# Bullseye_Volume_Board_Rev_0_0_3.net
KiCad netlist of a schematic drawn in Altium Designer
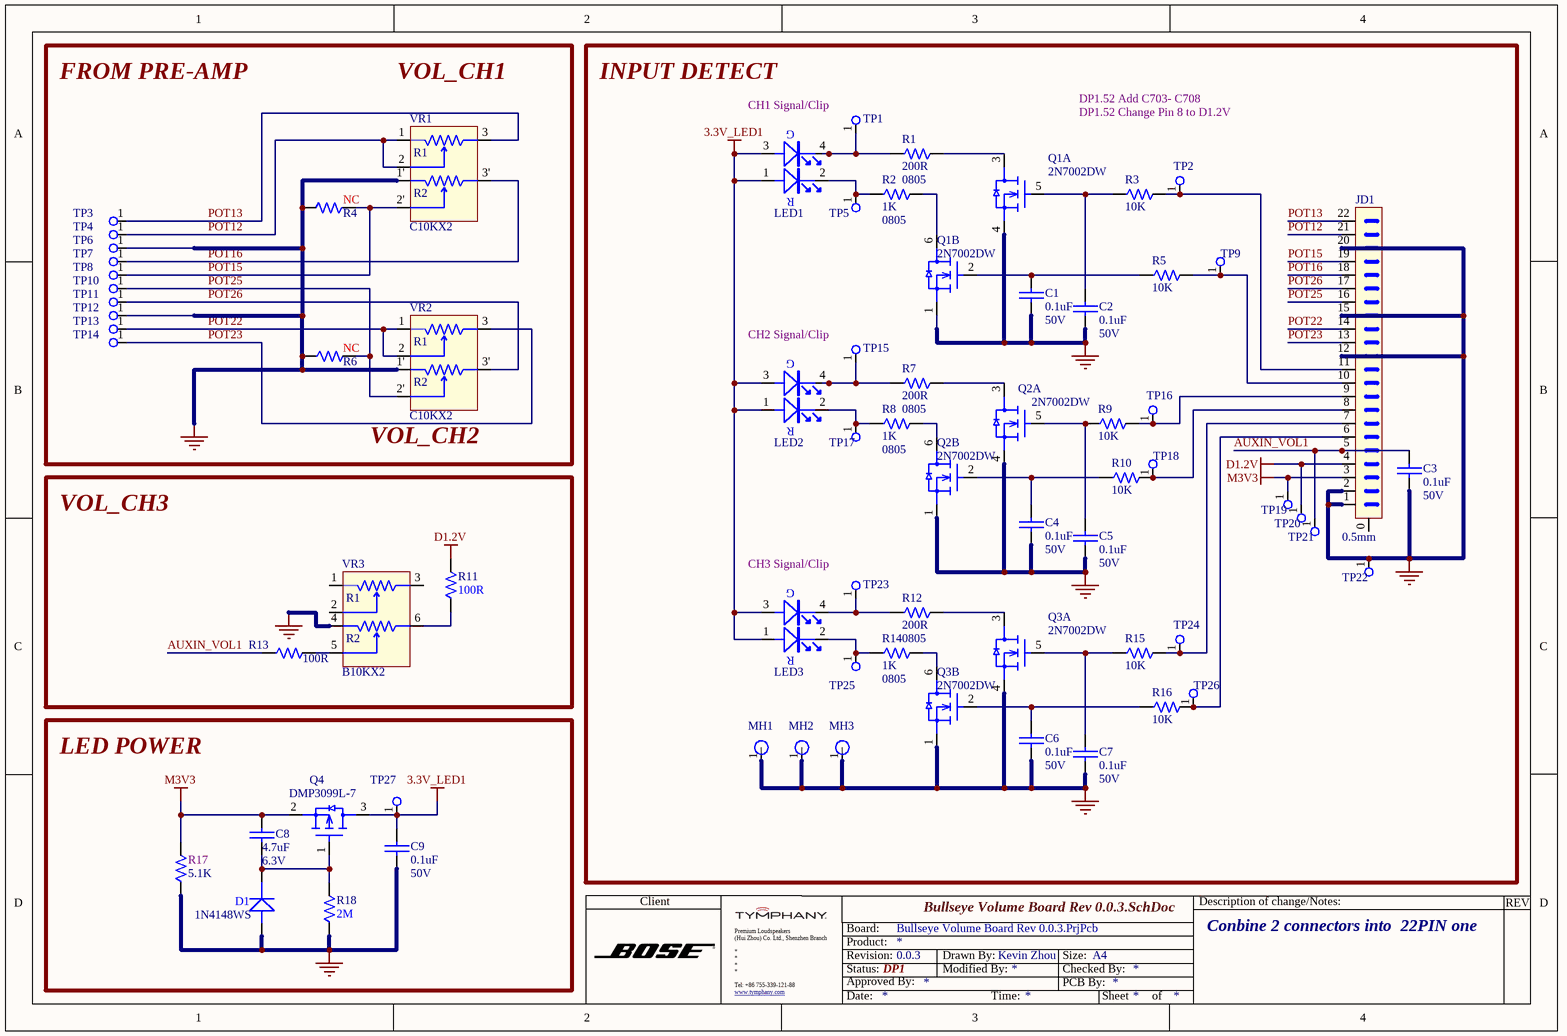
[diagram p0: Bullseye Volume Board Rev 0.0.3.SchDoc]

(export (version "E")
  (design (tool "Eeschema 10.0.6"))
  (components
    (comp (ref "C1")
      (value "0.1uF")
      (footprint "CAPC0402-RW")
      (description "CAP, CER, 0.1uF, 10%, 50V, X7R, 0402, RoHS")
      (fields
        (field (name "TOLERANCE") "10%")
        (field (name "VOLTAGE") "50V")
        (field (name "Comment") "PWL456470-1040")
        (field (name "CREATE_NAME") "TOM@Deftronics")
      )
      (libsource (lib "P-Capacitors") (part "CAP0402 0.1uF 50V 10%"))
    )
    (comp (ref "C2")
      (value "0.1uF")
      (footprint "CAPC0402-RW")
      (description "CAP, CER, 0.1uF, 10%, 50V, X7R, 0402, RoHS")
      (fields
        (field (name "TOLERANCE") "10%")
        (field (name "VOLTAGE") "50V")
        (field (name "Comment") "PWL456470-1040")
        (field (name "CREATE_NAME") "TOM@Deftronics")
      )
      (libsource (lib "P-Capacitors") (part "CAP0402 0.1uF 50V 10%"))
    )
    (comp (ref "C3")
      (value "0.1uF")
      (footprint "CAPC0402-RW")
      (description "CAP, CER, 0.1uF, 10%, 50V, X7R, 0402, RoHS")
      (fields
        (field (name "TOLERANCE") "10%")
        (field (name "VOLTAGE") "50V")
        (field (name "Comment") "PWL456470-1040")
        (field (name "CREATE_NAME") "TOM@Deftronics")
      )
      (libsource (lib "P-Capacitors") (part "CAP0402 0.1uF 50V 10%"))
    )
    (comp (ref "C4")
      (value "0.1uF")
      (footprint "CAPC0402-RW")
      (description "CAP, CER, 0.1uF, 10%, 50V, X7R, 0402, RoHS")
      (fields
        (field (name "TOLERANCE") "10%")
        (field (name "VOLTAGE") "50V")
        (field (name "Comment") "PWL456470-1040")
        (field (name "CREATE_NAME") "TOM@Deftronics")
      )
      (libsource (lib "P-Capacitors") (part "CAP0402 0.1uF 50V 10%"))
    )
    (comp (ref "C5")
      (value "0.1uF")
      (footprint "CAPC0402-RW")
      (description "CAP, CER, 0.1uF, 10%, 50V, X7R, 0402, RoHS")
      (fields
        (field (name "TOLERANCE") "10%")
        (field (name "VOLTAGE") "50V")
        (field (name "Comment") "PWL456470-1040")
        (field (name "CREATE_NAME") "TOM@Deftronics")
      )
      (libsource (lib "P-Capacitors") (part "CAP0402 0.1uF 50V 10%"))
    )
    (comp (ref "C6")
      (value "0.1uF")
      (footprint "CAPC0402-RW")
      (description "CAP, CER, 0.1uF, 10%, 50V, X7R, 0402, RoHS")
      (fields
        (field (name "TOLERANCE") "10%")
        (field (name "VOLTAGE") "50V")
        (field (name "Comment") "PWL456470-1040")
        (field (name "CREATE_NAME") "TOM@Deftronics")
      )
      (libsource (lib "P-Capacitors") (part "CAP0402 0.1uF 50V 10%"))
    )
    (comp (ref "C7")
      (value "0.1uF")
      (footprint "CAPC0402-RW")
      (description "CAP, CER, 0.1uF, 10%, 50V, X7R, 0402, RoHS")
      (fields
        (field (name "TOLERANCE") "10%")
        (field (name "VOLTAGE") "50V")
        (field (name "Comment") "PWL456470-1040")
        (field (name "CREATE_NAME") "TOM@Deftronics")
      )
      (libsource (lib "P-Capacitors") (part "CAP0402 0.1uF 50V 10%"))
    )
    (comp (ref "C8")
      (value "4.7uF")
      (footprint "CAPC0603-RW")
      (description "CHIP CAP 4.7uF 6.3V 10% 0603 TYPE X7R")
      (fields (field (name "MFG") "Walsin") (field (name "TOLERANCE") "10%") (field (name "VOLTAGE") "6.3V"))
      (libsource (lib "P-Capacitors") (part "CAP0603 4.7uF 6.3V 10% - Walsin"))
    )
    (comp (ref "C9")
      (value "0.1uF")
      (footprint "CAPC0603-RW")
      (description "GP CHIP CAP 0.1uF 50V 10% 0603 TYPE X7R")
      (fields
        (field (name "TOLERANCE") "10%")
        (field (name "VOLTAGE") "50V")
        (field (name "Comment") "PXL456470-1040")
      )
      (libsource (lib "P-Capacitors") (part "CAP0603 0.1uF 50V 10% - PXL456470-1040"))
    )
    (comp (ref "D1")
      (value "RCD114148-0020")
      (footprint "SOD-323")
      (description "DIODE SW 1N4148 VF=0.7V SOD-323")
      (fields
        (field (name "MFG") "TW SEMICONDUCTOR")
        (field (name "VOLTAGE") "100V")
        (field (name "MFG PART") "1N4148WS")
      )
      (libsource (lib "R-Semiconductors") (part "1N4148WS"))
    )
    (comp (ref "JD1")
      (value "0.5mm")
      (footprint "CONN FFC 22P PH=0.5mm SMT RA 0.5S-1X-22PWT-5.4R")
      (description "22P P=0.5MM 180 K")
      (fields
        (field (name "MFG") "金佳")
        (field (name "MFG PART") "0.5S-1X-22PWT-5.4R")
        (field (name "CREATE_NAME") "Nathan")
      )
      (libsource (lib "C-Connector") (part "CONN FFC 22P PH=0.5mm SMT RA 0.5S-1X-22PWT-5.4R"))
    )
    (comp (ref "LED1")
      (value "KCD250001-0010")
      (footprint "SMTLED2.0*1.25-RGB")
      (description "SMD LED 2.0x1.25mm MS-PTB2012CURSGAC  RED/GREEN")
      (fields
        (field (name "MFG PART") "MS-PTB2012CURSGAC  RED/GREEN")
        (field (name "MFG") "MASON")
        (field (name "CREATE_NAME") "TOM@Deftronics")
      )
      (libsource (lib "K-LED-FUSE") (part "MS-PTB2012CURSGAC"))
    )
    (comp (ref "LED2")
      (value "KCD250001-0010")
      (footprint "SMTLED2.0*1.25-RGB")
      (description "SMD LED 2.0x1.25mm MS-PTB2012CURSGAC  RED/GREEN")
      (fields
        (field (name "MFG PART") "MS-PTB2012CURSGAC  RED/GREEN")
        (field (name "MFG") "MASON")
        (field (name "CREATE_NAME") "TOM@Deftronics")
      )
      (libsource (lib "K-LED-FUSE") (part "MS-PTB2012CURSGAC"))
    )
    (comp (ref "LED3")
      (value "KCD250001-0010")
      (footprint "SMTLED2.0*1.25-RGB")
      (description "SMD LED 2.0x1.25mm MS-PTB2012CURSGAC  RED/GREEN")
      (fields
        (field (name "MFG PART") "MS-PTB2012CURSGAC  RED/GREEN")
        (field (name "MFG") "MASON")
        (field (name "CREATE_NAME") "TOM@Deftronics")
      )
      (libsource (lib "K-LED-FUSE") (part "MS-PTB2012CURSGAC"))
    )
    (comp (ref "MH1")
      (value "MHOLE 3MM")
      (footprint "MHOLE 3.5MM W/Vias")
      (description "MOUNTING HOLE FOR 3MM SCREW")
      (libsource (lib "Temporary") (part "MHOLE 3MM"))
    )
    (comp (ref "MH2")
      (value "MHOLE 3MM")
      (footprint "MHOLE 3.5MM W/Vias")
      (description "MOUNTING HOLE FOR 3MM SCREW")
      (libsource (lib "Temporary") (part "MHOLE 3MM"))
    )
    (comp (ref "MH3")
      (value "MHOLE 3MM")
      (footprint "MHOLE 3.5MM W/Vias")
      (description "MOUNTING HOLE FOR 3MM SCREW")
      (libsource (lib "Temporary") (part "MHOLE 3MM"))
    )
    (comp (ref "Q1")
      (value "RCM027002-1001")
      (footprint "SOT-363")
      (description "SMD MOSFET N-CH SOT-363 2N7002DW      Fairchild")
      (fields
        (field (name "MFG") "Fairchild")
        (field (name "MFG_PART") "2N7002DW")
        (field (name "CREATE_NAME") "Evan@Deftronics")
      )
      (libsource (lib "R-Semiconductors") (part "2N7002DW"))
    )
    (comp (ref "Q2")
      (value "RCM027002-1001")
      (footprint "SOT-363")
      (description "SMD MOSFET N-CH SOT-363 2N7002DW      Fairchild")
      (fields
        (field (name "MFG") "Fairchild")
        (field (name "MFG_PART") "2N7002DW")
        (field (name "CREATE_NAME") "Evan@Deftronics")
      )
      (libsource (lib "R-Semiconductors") (part "2N7002DW"))
    )
    (comp (ref "Q3")
      (value "RCM027002-1001")
      (footprint "SOT-363")
      (description "SMD MOSFET N-CH SOT-363 2N7002DW      Fairchild")
      (fields
        (field (name "MFG") "Fairchild")
        (field (name "MFG_PART") "2N7002DW")
        (field (name "CREATE_NAME") "Evan@Deftronics")
      )
      (libsource (lib "R-Semiconductors") (part "2N7002DW"))
    )
    (comp (ref "Q4")
      (value "T585002550438")
      (footprint "SOT23-132-RW")
      (description "PMOS 20V DMP3099L-7 SOT23 DIODES K")
      (fields
        (field (name "MFG") "DIODES  (ZETEX)")
        (field (name "MFG PART") "DMP3099L-7")
        (field (name "CREATE_NAME") "Nathan")
      )
      (libsource (lib "R-Semiconductors") (part "DMP3099L-7"))
    )
    (comp (ref "R1")
      (value "200R")
      (footprint "0805-RW")
      (description "GP CHIP RES. 200 OHM 1/8W 1% 0805")
      (fields (field (name "PACKAGE") "0805") (field (name "Comment") "QCF081020-2000"))
      (libsource (lib "Q-Resistors") (part "RES0805 1/8W 1% 200 OHM"))
    )
    (comp (ref "R2")
      (value "1K")
      (footprint "0805-RW")
      (description "GP CHIP RES. 1K OHM 1/8W 1% 0805")
      (fields (field (name "PACKAGE") "0805") (field (name "Comment") "QCF081020-1001"))
      (libsource (lib "Q-Resistors") (part "RES0805 1/8W 1% 1K OHM"))
    )
    (comp (ref "R3")
      (value "10K")
      (footprint "0402-RW")
      (description "CHIP RES 10K OHM 1/16W 1% 0402")
      (fields (field (name "MFG") "WALSIN") (field (name "Comment") "QCF161240-1002"))
      (libsource (lib "Q-Resistors") (part "RES0402 1/16W 1% 10K OHM"))
    )
    (comp (ref "R4")
      (value "NC")
      (footprint "0603-RW")
      (fields (field (name "Comment") "RES0603 NC") (field (name "CREATE_NAME") "Tom"))
      (libsource (lib "Temporary") (part "RES0603 NC"))
    )
    (comp (ref "R5")
      (value "10K")
      (footprint "0402-RW")
      (description "CHIP RES 10K OHM 1/16W 1% 0402")
      (fields (field (name "MFG") "WALSIN") (field (name "Comment") "QCF161240-1002"))
      (libsource (lib "Q-Resistors") (part "RES0402 1/16W 1% 10K OHM"))
    )
    (comp (ref "R6")
      (value "NC")
      (footprint "0603-RW")
      (fields (field (name "Comment") "RES0603 NC") (field (name "CREATE_NAME") "Tom"))
      (libsource (lib "Temporary") (part "RES0603 NC"))
    )
    (comp (ref "R7")
      (value "200R")
      (footprint "0805-RW")
      (description "GP CHIP RES. 200 OHM 1/8W 1% 0805")
      (fields (field (name "PACKAGE") "0805") (field (name "Comment") "QCF081020-2000"))
      (libsource (lib "Q-Resistors") (part "RES0805 1/8W 1% 200 OHM"))
    )
    (comp (ref "R8")
      (value "1K")
      (footprint "0805-RW")
      (description "GP CHIP RES. 1K OHM 1/8W 1% 0805")
      (fields (field (name "PACKAGE") "0805") (field (name "Comment") "QCF081020-1001"))
      (libsource (lib "Q-Resistors") (part "RES0805 1/8W 1% 1K OHM"))
    )
    (comp (ref "R9")
      (value "10K")
      (footprint "0402-RW")
      (description "CHIP RES 10K OHM 1/16W 1% 0402")
      (fields (field (name "MFG") "WALSIN") (field (name "Comment") "QCF161240-1002"))
      (libsource (lib "Q-Resistors") (part "RES0402 1/16W 1% 10K OHM"))
    )
    (comp (ref "R10")
      (value "10K")
      (footprint "0402-RW")
      (description "CHIP RES 10K OHM 1/16W 1% 0402")
      (fields (field (name "MFG") "WALSIN") (field (name "Comment") "QCF161240-1002"))
      (libsource (lib "Q-Resistors") (part "RES0402 1/16W 1% 10K OHM"))
    )
    (comp (ref "R11")
      (value "100R")
      (footprint "0402-RW")
      (description "CHIP RES 100 OHM 1/16W 1% 0402")
      (fields (field (name "MFG") "WALSIN") (field (name "Comment") "QCF161240-1000"))
      (libsource (lib "Q-Resistors") (part "RES0402 1/16W 1% 100 OHM"))
    )
    (comp (ref "R12")
      (value "200R")
      (footprint "0805-RW")
      (description "GP CHIP RES. 200 OHM 1/8W 1% 0805")
      (fields (field (name "PACKAGE") "0805") (field (name "Comment") "QCF081020-2000"))
      (libsource (lib "Q-Resistors") (part "RES0805 1/8W 1% 200 OHM"))
    )
    (comp (ref "R13")
      (value "100R")
      (footprint "0402-RW")
      (description "CHIP RES 100 OHM 1/16W 1% 0402")
      (fields (field (name "POWER") "1/16W") (field (name "MFG") "WALSIN"))
      (libsource (lib "Q-Resistors") (part "RES0402 1/16W 1% 100 OHM"))
    )
    (comp (ref "R14")
      (value "1K")
      (footprint "0805-RW")
      (description "GP CHIP RES. 1K OHM 1/8W 1% 0805")
      (fields (field (name "PACKAGE") "0805") (field (name "Comment") "QCF081020-1001"))
      (libsource (lib "Q-Resistors") (part "RES0805 1/8W 1% 1K OHM"))
    )
    (comp (ref "R15")
      (value "10K")
      (footprint "0402-RW")
      (description "CHIP RES 10K OHM 1/16W 1% 0402")
      (fields (field (name "MFG") "WALSIN") (field (name "Comment") "QCF161240-1002"))
      (libsource (lib "Q-Resistors") (part "RES0402 1/16W 1% 10K OHM"))
    )
    (comp (ref "R16")
      (value "10K")
      (footprint "0402-RW")
      (description "CHIP RES 10K OHM 1/16W 1% 0402")
      (fields (field (name "MFG") "WALSIN") (field (name "Comment") "QCF161240-1002"))
      (libsource (lib "Q-Resistors") (part "RES0402 1/16W 1% 10K OHM"))
    )
    (comp (ref "R17")
      (value "5.1K")
      (footprint "0603-RW")
      (description "GP CHIP RES. 5.1K OHM 1/10W 1% 0603")
      (fields (field (name "Comment") "QCF011030-5101"))
      (libsource (lib "Q-Resistors") (part "RES0603 1/10W 1% 5.1K OHM"))
    )
    (comp (ref "R18")
      (value "2M")
      (footprint "0402-RW")
      (description "CHIP 2M OHM    100PPM +-1% 0402 WALS L")
      (fields
        (field (name "MFG") "WALSIN (華新)")
        (field (name "POWER") "1/16W")
        (field (name "CREATE_NAME") "Nathan")
      )
      (libsource (lib "Q-Resistors") (part "RES0402 1/16W 1% 2M OMH_WALSIN"))
    )
    (comp (ref "TP1")
      (value "CH1_GN")
      (footprint "TP_1.2mm")
      (description "TP")
      (libsource (lib "Temporary") (part "TP"))
    )
    (comp (ref "TP2")
      (value "CH1_SIG")
      (footprint "TP_1.2mm")
      (description "TP")
      (libsource (lib "Temporary") (part "TP"))
    )
    (comp (ref "TP3")
      (value "CH1_GN")
      (footprint "TP_1.2mm")
      (description "TP")
      (libsource (lib "Temporary") (part "TP"))
    )
    (comp (ref "TP4")
      (value "CH1_GN")
      (footprint "TP_1.2mm")
      (description "TP")
      (libsource (lib "Temporary") (part "TP"))
    )
    (comp (ref "TP5")
      (value "CH1_RED")
      (footprint "TP_1.2mm")
      (description "TP")
      (libsource (lib "Temporary") (part "TP"))
    )
    (comp (ref "TP6")
      (value "CH1_GN")
      (footprint "TP_1.2mm")
      (description "TP")
      (libsource (lib "Temporary") (part "TP"))
    )
    (comp (ref "TP7")
      (value "CH1_GN")
      (footprint "TP_1.2mm")
      (description "TP")
      (libsource (lib "Temporary") (part "TP"))
    )
    (comp (ref "TP8")
      (value "CH1_GN")
      (footprint "TP_1.2mm")
      (description "TP")
      (libsource (lib "Temporary") (part "TP"))
    )
    (comp (ref "TP9")
      (value "CH1_LIM")
      (footprint "TP_1.2mm")
      (description "TP")
      (libsource (lib "Temporary") (part "TP"))
    )
    (comp (ref "TP10")
      (value "CH1_GN")
      (footprint "TP_1.2mm")
      (description "TP")
      (libsource (lib "Temporary") (part "TP"))
    )
    (comp (ref "TP11")
      (value "CH1_GN")
      (footprint "TP_1.2mm")
      (description "TP")
      (libsource (lib "Temporary") (part "TP"))
    )
    (comp (ref "TP12")
      (value "CH1_GN")
      (footprint "TP_1.2mm")
      (description "TP")
      (libsource (lib "Temporary") (part "TP"))
    )
    (comp (ref "TP13")
      (value "CH1_GN")
      (footprint "TP_1.2mm")
      (description "TP")
      (libsource (lib "Temporary") (part "TP"))
    )
    (comp (ref "TP14")
      (value "CH1_GN")
      (footprint "TP_1.2mm")
      (description "TP")
      (libsource (lib "Temporary") (part "TP"))
    )
    (comp (ref "TP15")
      (value "CH1_GN")
      (footprint "TP_1.2mm")
      (description "TP")
      (libsource (lib "Temporary") (part "TP"))
    )
    (comp (ref "TP16")
      (value "CH1_SIG")
      (footprint "TP_1.2mm")
      (description "TP")
      (libsource (lib "Temporary") (part "TP"))
    )
    (comp (ref "TP17")
      (value "CH1_RED")
      (footprint "TP_1.2mm")
      (description "TP")
      (libsource (lib "Temporary") (part "TP"))
    )
    (comp (ref "TP18")
      (value "CH1_LIM")
      (footprint "TP_1.2mm")
      (description "TP")
      (libsource (lib "Temporary") (part "TP"))
    )
    (comp (ref "TP19")
      (value "CH1_LIM")
      (footprint "TP_1.2mm")
      (description "TP")
      (libsource (lib "Temporary") (part "TP"))
    )
    (comp (ref "TP20")
      (value "CH1_LIM")
      (footprint "TP_1.2mm")
      (description "TP")
      (libsource (lib "Temporary") (part "TP"))
    )
    (comp (ref "TP21")
      (value "CH1_LIM")
      (footprint "TP_1.2mm")
      (description "TP")
      (libsource (lib "Temporary") (part "TP"))
    )
    (comp (ref "TP22")
      (value "CH1_LIM")
      (footprint "TP_1.2mm")
      (description "TP")
      (libsource (lib "Temporary") (part "TP"))
    )
    (comp (ref "TP23")
      (value "CH1_GN")
      (footprint "TP_1.2mm")
      (description "TP")
      (libsource (lib "Temporary") (part "TP"))
    )
    (comp (ref "TP24")
      (value "CH1_SIG")
      (footprint "TP_1.2mm")
      (description "TP")
      (libsource (lib "Temporary") (part "TP"))
    )
    (comp (ref "TP25")
      (value "CH1_RED")
      (footprint "TP_1.2mm")
      (description "TP")
      (libsource (lib "Temporary") (part "TP"))
    )
    (comp (ref "TP26")
      (value "CH1_LIM")
      (footprint "TP_1.2mm")
      (description "TP")
      (libsource (lib "Temporary") (part "TP"))
    )
    (comp (ref "TP27")
      (value "CH2_SIG")
      (footprint "TP_1.2mm")
      (description "TP")
      (libsource (lib "Temporary") (part "TP"))
    )
    (comp (ref "VR1")
      (value "C10KX2")
      (footprint "R11122G-FA20B7-5C103-167")
      (description "VR CA 10K C L=20MM R11122G-F K")
      (fields
        (field (name "MFG") "IDEAL")
        (field (name "MFG PART") "R11122G-FA20B7-5C103-167")
        (field (name "CREATE_NAME") "Nathan")
      )
      (libsource (lib "M-Controls") (part "R11122G-FA20B7-5C103-167"))
    )
    (comp (ref "VR2")
      (value "C10KX2")
      (footprint "R11122G-FA20B7-5C103-167")
      (description "VR CA 10K C L=20MM R11122G-F K")
      (fields
        (field (name "MFG") "IDEAL")
        (field (name "MFG PART") "R11122G-FA20B7-5C103-167")
        (field (name "CREATE_NAME") "Nathan")
      )
      (libsource (lib "M-Controls") (part "R11122G-FA20B7-5C103-167"))
    )
    (comp (ref "VR3")
      (value "B10KX2")
      (footprint "RV112BCF-40-20A-B10K-0C")
      (description "VR CA 10K B 15.4X13MM RV112BCF- K")
      (fields
        (field (name "MFG") "ALPHA    (東莞艾華電子)")
        (field (name "MFG PART") "RV112BCF-40-20A-B10K-0C")
        (field (name "CREATE_NAME") "Nathan")
      )
      (libsource (lib "M-Controls") (part "RV112BCF-40-20A-B10K-0C"))
    )
  )
  (nets
    (net (code "1") (name "/AUXIN_VOL1") (class "Default")
      (node (ref "C3") (pin "1") (pinfunction "1_1") (pintype "passive"))
      (node (ref "JD1") (pin "5") (pinfunction "5_5") (pintype "passive"))
      (node (ref "R13") (pin "1") (pinfunction "1_1") (pintype "passive"))
      (node (ref "TP21") (pin "1") (pinfunction "1_1") (pintype "passive"))
    )
    (net (code "2") (name "/POT12") (class "Default")
      (node (ref "JD1") (pin "21") (pinfunction "21_21") (pintype "passive"))
      (node (ref "TP4") (pin "1") (pinfunction "1_1") (pintype "passive"))
      (node (ref "VR1") (pin "1") (pinfunction "1_1") (pintype "passive"))
      (node (ref "VR1") (pin "2") (pinfunction "2_2") (pintype "passive"))
    )
    (net (code "3") (name "/POT13") (class "Default")
      (node (ref "JD1") (pin "22") (pinfunction "22_22") (pintype "passive"))
      (node (ref "TP3") (pin "1") (pinfunction "1_1") (pintype "passive"))
      (node (ref "VR1") (pin "3") (pinfunction "3_3") (pintype "passive"))
    )
    (net (code "4") (name "/POT15") (class "Default")
      (node (ref "JD1") (pin "19") (pinfunction "19_19") (pintype "passive"))
      (node (ref "R4") (pin "1") (pinfunction "1_1") (pintype "passive"))
      (node (ref "TP8") (pin "1") (pinfunction "1_1") (pintype "passive"))
      (node (ref "VR1") (pin "2'") (pinfunction "2'_2'") (pintype "passive"))
    )
    (net (code "5") (name "/POT16") (class "Default")
      (node (ref "JD1") (pin "18") (pinfunction "18_18") (pintype "passive"))
      (node (ref "TP7") (pin "1") (pinfunction "1_1") (pintype "passive"))
      (node (ref "VR1") (pin "3'") (pinfunction "3'_3'") (pintype "passive"))
    )
    (net (code "6") (name "/POT22") (class "Default")
      (node (ref "JD1") (pin "14") (pinfunction "14_14") (pintype "passive"))
      (node (ref "TP13") (pin "1") (pinfunction "1_1") (pintype "passive"))
      (node (ref "VR2") (pin "1") (pinfunction "1_1") (pintype "passive"))
      (node (ref "VR2") (pin "2") (pinfunction "2_2") (pintype "passive"))
    )
    (net (code "7") (name "/POT23") (class "Default")
      (node (ref "JD1") (pin "13") (pinfunction "13_13") (pintype "passive"))
      (node (ref "TP14") (pin "1") (pinfunction "1_1") (pintype "passive"))
      (node (ref "VR2") (pin "3") (pinfunction "3_3") (pintype "passive"))
    )
    (net (code "8") (name "/POT25") (class "Default")
      (node (ref "JD1") (pin "16") (pinfunction "16_16") (pintype "passive"))
      (node (ref "R6") (pin "2") (pinfunction "2_2") (pintype "passive"))
      (node (ref "TP10") (pin "1") (pinfunction "1_1") (pintype "passive"))
      (node (ref "VR2") (pin "2'") (pinfunction "2'_2'") (pintype "passive"))
    )
    (net (code "9") (name "/POT26") (class "Default")
      (node (ref "JD1") (pin "17") (pinfunction "17_17") (pintype "passive"))
      (node (ref "TP11") (pin "1") (pinfunction "1_1") (pintype "passive"))
      (node (ref "VR2") (pin "3'") (pinfunction "3'_3'") (pintype "passive"))
    )
    (net (code "10") (name "3.3V_LED1") (class "Default")
      (node (ref "C9") (pin "2") (pinfunction "2_2") (pintype "passive"))
      (node (ref "LED1") (pin "1") (pinfunction "1_1") (pintype "passive"))
      (node (ref "LED1") (pin "3") (pinfunction "3_3") (pintype "passive"))
      (node (ref "LED2") (pin "1") (pinfunction "1_1") (pintype "passive"))
      (node (ref "LED2") (pin "3") (pinfunction "3_3") (pintype "passive"))
      (node (ref "LED3") (pin "1") (pinfunction "1_1") (pintype "passive"))
      (node (ref "LED3") (pin "3") (pinfunction "3_3") (pintype "passive"))
      (node (ref "Q4") (pin "3") (pinfunction "D_3") (pintype "passive"))
      (node (ref "TP27") (pin "1") (pinfunction "1_1") (pintype "passive"))
    )
    (net (code "11") (name "D1.2V") (class "Default")
      (node (ref "JD1") (pin "4") (pinfunction "4_4") (pintype "passive"))
      (node (ref "R11") (pin "2") (pinfunction "2_2") (pintype "passive"))
      (node (ref "TP20") (pin "1") (pinfunction "1_1") (pintype "passive"))
    )
    (net (code "12") (name "GND") (class "Default")
      (node (ref "C1") (pin "2") (pinfunction "2_2") (pintype "passive"))
      (node (ref "C2") (pin "2") (pinfunction "2_2") (pintype "passive"))
      (node (ref "C3") (pin "2") (pinfunction "2_2") (pintype "passive"))
      (node (ref "C4") (pin "2") (pinfunction "2_2") (pintype "passive"))
      (node (ref "C5") (pin "2") (pinfunction "2_2") (pintype "passive"))
      (node (ref "C6") (pin "2") (pinfunction "2_2") (pintype "passive"))
      (node (ref "C7") (pin "2") (pinfunction "2_2") (pintype "passive"))
      (node (ref "C9") (pin "1") (pinfunction "1_1") (pintype "passive"))
      (node (ref "D1") (pin "1") (pinfunction "A_1") (pintype "passive"))
      (node (ref "JD1") (pin "1") (pinfunction "1_1") (pintype "passive"))
      (node (ref "JD1") (pin "12") (pinfunction "12_12") (pintype "passive"))
      (node (ref "JD1") (pin "15") (pinfunction "15_15") (pintype "passive"))
      (node (ref "JD1") (pin "2") (pinfunction "2_2") (pintype "passive"))
      (node (ref "JD1") (pin "20") (pinfunction "20_20") (pintype "passive"))
      (node (ref "MH1") (pin "1") (pinfunction "1_1") (pintype "passive"))
      (node (ref "MH2") (pin "1") (pinfunction "1_1") (pintype "passive"))
      (node (ref "MH3") (pin "1") (pinfunction "1_1") (pintype "passive"))
      (node (ref "Q1") (pin "1") (pinfunction "S_1") (pintype "passive"))
      (node (ref "Q1") (pin "4") (pinfunction "S_4") (pintype "passive"))
      (node (ref "Q2") (pin "1") (pinfunction "S_1") (pintype "passive"))
      (node (ref "Q2") (pin "4") (pinfunction "S_4") (pintype "passive"))
      (node (ref "Q3") (pin "1") (pinfunction "S_1") (pintype "passive"))
      (node (ref "Q3") (pin "4") (pinfunction "S_4") (pintype "passive"))
      (node (ref "R17") (pin "1") (pinfunction "1_1") (pintype "passive"))
      (node (ref "R18") (pin "1") (pinfunction "1_1") (pintype "passive"))
      (node (ref "R4") (pin "2") (pinfunction "2_2") (pintype "passive"))
      (node (ref "R6") (pin "1") (pinfunction "1_1") (pintype "passive"))
      (node (ref "TP12") (pin "1") (pinfunction "1_1") (pintype "passive"))
      (node (ref "TP22") (pin "1") (pinfunction "1_1") (pintype "passive"))
      (node (ref "TP6") (pin "1") (pinfunction "1_1") (pintype "passive"))
      (node (ref "VR1") (pin "1'") (pinfunction "1'_1'") (pintype "passive"))
      (node (ref "VR2") (pin "1'") (pinfunction "1'_1'") (pintype "passive"))
      (node (ref "VR3") (pin "4") (pinfunction "4_4") (pintype "passive"))
    )
    (net (code "13") (name "M3V3") (class "Default")
      (node (ref "C8") (pin "1") (pinfunction "1_1") (pintype "passive"))
      (node (ref "JD1") (pin "3") (pinfunction "3_3") (pintype "passive"))
      (node (ref "Q4") (pin "2") (pinfunction "S_2") (pintype "passive"))
      (node (ref "R17") (pin "2") (pinfunction "2_2") (pintype "passive"))
      (node (ref "TP19") (pin "1") (pinfunction "1_1") (pintype "passive"))
    )
    (net (code "14") (name "Net-(D1-K)") (class "Default")
      (node (ref "C8") (pin "2") (pinfunction "2_2") (pintype "passive"))
      (node (ref "D1") (pin "2") (pinfunction "K_2") (pintype "passive"))
      (node (ref "Q4") (pin "1") (pinfunction "G_1") (pintype "passive"))
      (node (ref "R18") (pin "2") (pinfunction "2_2") (pintype "passive"))
    )
    (net (code "15") (name "Net-(JD1-Pad6)") (class "Default")
      (node (ref "JD1") (pin "6") (pinfunction "6_6") (pintype "passive"))
      (node (ref "R16") (pin "2") (pinfunction "2_2") (pintype "passive"))
      (node (ref "TP26") (pin "1") (pinfunction "1_1") (pintype "passive"))
    )
    (net (code "16") (name "Net-(JD1-Pad7)") (class "Default")
      (node (ref "JD1") (pin "7") (pinfunction "7_7") (pintype "passive"))
      (node (ref "R15") (pin "2") (pinfunction "2_2") (pintype "passive"))
      (node (ref "TP24") (pin "1") (pinfunction "1_1") (pintype "passive"))
    )
    (net (code "17") (name "Net-(JD1-Pad8)") (class "Default")
      (node (ref "JD1") (pin "8") (pinfunction "8_8") (pintype "passive"))
      (node (ref "R10") (pin "2") (pinfunction "2_2") (pintype "passive"))
      (node (ref "TP18") (pin "1") (pinfunction "1_1") (pintype "passive"))
    )
    (net (code "18") (name "Net-(JD1-Pad9)") (class "Default")
      (node (ref "JD1") (pin "9") (pinfunction "9_9") (pintype "passive"))
      (node (ref "R9") (pin "2") (pinfunction "2_2") (pintype "passive"))
      (node (ref "TP16") (pin "1") (pinfunction "1_1") (pintype "passive"))
    )
    (net (code "19") (name "Net-(JD1-Pad10)") (class "Default")
      (node (ref "JD1") (pin "10") (pinfunction "10_10") (pintype "passive"))
      (node (ref "R5") (pin "2") (pinfunction "2_2") (pintype "passive"))
      (node (ref "TP9") (pin "1") (pinfunction "1_1") (pintype "passive"))
    )
    (net (code "20") (name "Net-(JD1-Pad11)") (class "Default")
      (node (ref "JD1") (pin "11") (pinfunction "11_11") (pintype "passive"))
      (node (ref "R3") (pin "2") (pinfunction "2_2") (pintype "passive"))
      (node (ref "TP2") (pin "1") (pinfunction "1_1") (pintype "passive"))
    )
    (net (code "21") (name "Net-(LED1-Pad2)") (class "Default")
      (node (ref "LED1") (pin "2") (pinfunction "2_2") (pintype "passive"))
      (node (ref "R2") (pin "1") (pinfunction "1_1") (pintype "passive"))
      (node (ref "TP5") (pin "1") (pinfunction "1_1") (pintype "passive"))
    )
    (net (code "22") (name "Net-(LED1-Pad4)") (class "Default")
      (node (ref "LED1") (pin "4") (pinfunction "4_4") (pintype "passive"))
      (node (ref "R1") (pin "1") (pinfunction "1_1") (pintype "passive"))
      (node (ref "TP1") (pin "1") (pinfunction "1_1") (pintype "passive"))
    )
    (net (code "23") (name "Net-(LED2-Pad2)") (class "Default")
      (node (ref "LED2") (pin "2") (pinfunction "2_2") (pintype "passive"))
      (node (ref "R8") (pin "1") (pinfunction "1_1") (pintype "passive"))
      (node (ref "TP17") (pin "1") (pinfunction "1_1") (pintype "passive"))
    )
    (net (code "24") (name "Net-(LED2-Pad4)") (class "Default")
      (node (ref "LED2") (pin "4") (pinfunction "4_4") (pintype "passive"))
      (node (ref "R7") (pin "1") (pinfunction "1_1") (pintype "passive"))
      (node (ref "TP15") (pin "1") (pinfunction "1_1") (pintype "passive"))
    )
    (net (code "25") (name "Net-(LED3-Pad2)") (class "Default")
      (node (ref "LED3") (pin "2") (pinfunction "2_2") (pintype "passive"))
      (node (ref "R14") (pin "1") (pinfunction "1_1") (pintype "passive"))
      (node (ref "TP25") (pin "1") (pinfunction "1_1") (pintype "passive"))
    )
    (net (code "26") (name "Net-(LED3-Pad4)") (class "Default")
      (node (ref "LED3") (pin "4") (pinfunction "4_4") (pintype "passive"))
      (node (ref "R12") (pin "1") (pinfunction "1_1") (pintype "passive"))
      (node (ref "TP23") (pin "1") (pinfunction "1_1") (pintype "passive"))
    )
    (net (code "27") (name "Net-(Q1A-D)") (class "Default")
      (node (ref "Q1") (pin "3") (pinfunction "D_3") (pintype "passive"))
      (node (ref "R1") (pin "2") (pinfunction "2_2") (pintype "passive"))
    )
    (net (code "28") (name "Net-(Q1A-G)") (class "Default")
      (node (ref "C2") (pin "1") (pinfunction "1_1") (pintype "passive"))
      (node (ref "Q1") (pin "5") (pinfunction "G_5") (pintype "passive"))
      (node (ref "R3") (pin "1") (pinfunction "1_1") (pintype "passive"))
    )
    (net (code "29") (name "Net-(Q1B-D)") (class "Default")
      (node (ref "Q1") (pin "6") (pinfunction "D_6") (pintype "passive"))
      (node (ref "R2") (pin "2") (pinfunction "2_2") (pintype "passive"))
    )
    (net (code "30") (name "Net-(Q1B-G)") (class "Default")
      (node (ref "C1") (pin "1") (pinfunction "1_1") (pintype "passive"))
      (node (ref "Q1") (pin "2") (pinfunction "G_2") (pintype "passive"))
      (node (ref "R5") (pin "1") (pinfunction "1_1") (pintype "passive"))
    )
    (net (code "31") (name "Net-(Q2A-D)") (class "Default")
      (node (ref "Q2") (pin "3") (pinfunction "D_3") (pintype "passive"))
      (node (ref "R7") (pin "2") (pinfunction "2_2") (pintype "passive"))
    )
    (net (code "32") (name "Net-(Q2A-G)") (class "Default")
      (node (ref "C5") (pin "1") (pinfunction "1_1") (pintype "passive"))
      (node (ref "Q2") (pin "5") (pinfunction "G_5") (pintype "passive"))
      (node (ref "R9") (pin "1") (pinfunction "1_1") (pintype "passive"))
    )
    (net (code "33") (name "Net-(Q2B-D)") (class "Default")
      (node (ref "Q2") (pin "6") (pinfunction "D_6") (pintype "passive"))
      (node (ref "R8") (pin "2") (pinfunction "2_2") (pintype "passive"))
    )
    (net (code "34") (name "Net-(Q2B-G)") (class "Default")
      (node (ref "C4") (pin "1") (pinfunction "1_1") (pintype "passive"))
      (node (ref "Q2") (pin "2") (pinfunction "G_2") (pintype "passive"))
      (node (ref "R10") (pin "1") (pinfunction "1_1") (pintype "passive"))
    )
    (net (code "35") (name "Net-(Q3A-D)") (class "Default")
      (node (ref "Q3") (pin "3") (pinfunction "D_3") (pintype "passive"))
      (node (ref "R12") (pin "2") (pinfunction "2_2") (pintype "passive"))
    )
    (net (code "36") (name "Net-(Q3A-G)") (class "Default")
      (node (ref "C7") (pin "1") (pinfunction "1_1") (pintype "passive"))
      (node (ref "Q3") (pin "5") (pinfunction "G_5") (pintype "passive"))
      (node (ref "R15") (pin "1") (pinfunction "1_1") (pintype "passive"))
    )
    (net (code "37") (name "Net-(Q3B-D)") (class "Default")
      (node (ref "Q3") (pin "6") (pinfunction "D_6") (pintype "passive"))
      (node (ref "R14") (pin "2") (pinfunction "2_2") (pintype "passive"))
    )
    (net (code "38") (name "Net-(Q3B-G)") (class "Default")
      (node (ref "C6") (pin "1") (pinfunction "1_1") (pintype "passive"))
      (node (ref "Q3") (pin "2") (pinfunction "G_2") (pintype "passive"))
      (node (ref "R16") (pin "1") (pinfunction "1_1") (pintype "passive"))
    )
    (net (code "39") (name "Net-(R11-Pad1)") (class "Default")
      (node (ref "R11") (pin "1") (pinfunction "1_1") (pintype "passive"))
      (node (ref "VR3") (pin "6") (pinfunction "6_6") (pintype "passive"))
    )
    (net (code "40") (name "Net-(R13-Pad2)") (class "Default")
      (node (ref "R13") (pin "2") (pinfunction "2_2") (pintype "passive"))
      (node (ref "VR3") (pin "5") (pinfunction "5_5") (pintype "passive"))
    )
    (net (code "41") (name "unconnected-(JD1-Pad0)") (class "Default")
      (node (ref "JD1") (pin "0") (pinfunction "0_0") (pintype "passive"))
    )
    (net (code "42") (name "unconnected-(VR3-Pad1)") (class "Default")
      (node (ref "VR3") (pin "1") (pinfunction "1_1") (pintype "passive"))
    )
    (net (code "43") (name "unconnected-(VR3-Pad2)") (class "Default")
      (node (ref "VR3") (pin "2") (pinfunction "2_2") (pintype "passive"))
    )
    (net (code "44") (name "unconnected-(VR3-Pad3)") (class "Default")
      (node (ref "VR3") (pin "3") (pinfunction "3_3") (pintype "passive"))
    )
  )
)
